# usb2serial.net
KiCad netlist of a schematic drawn in EAGLE
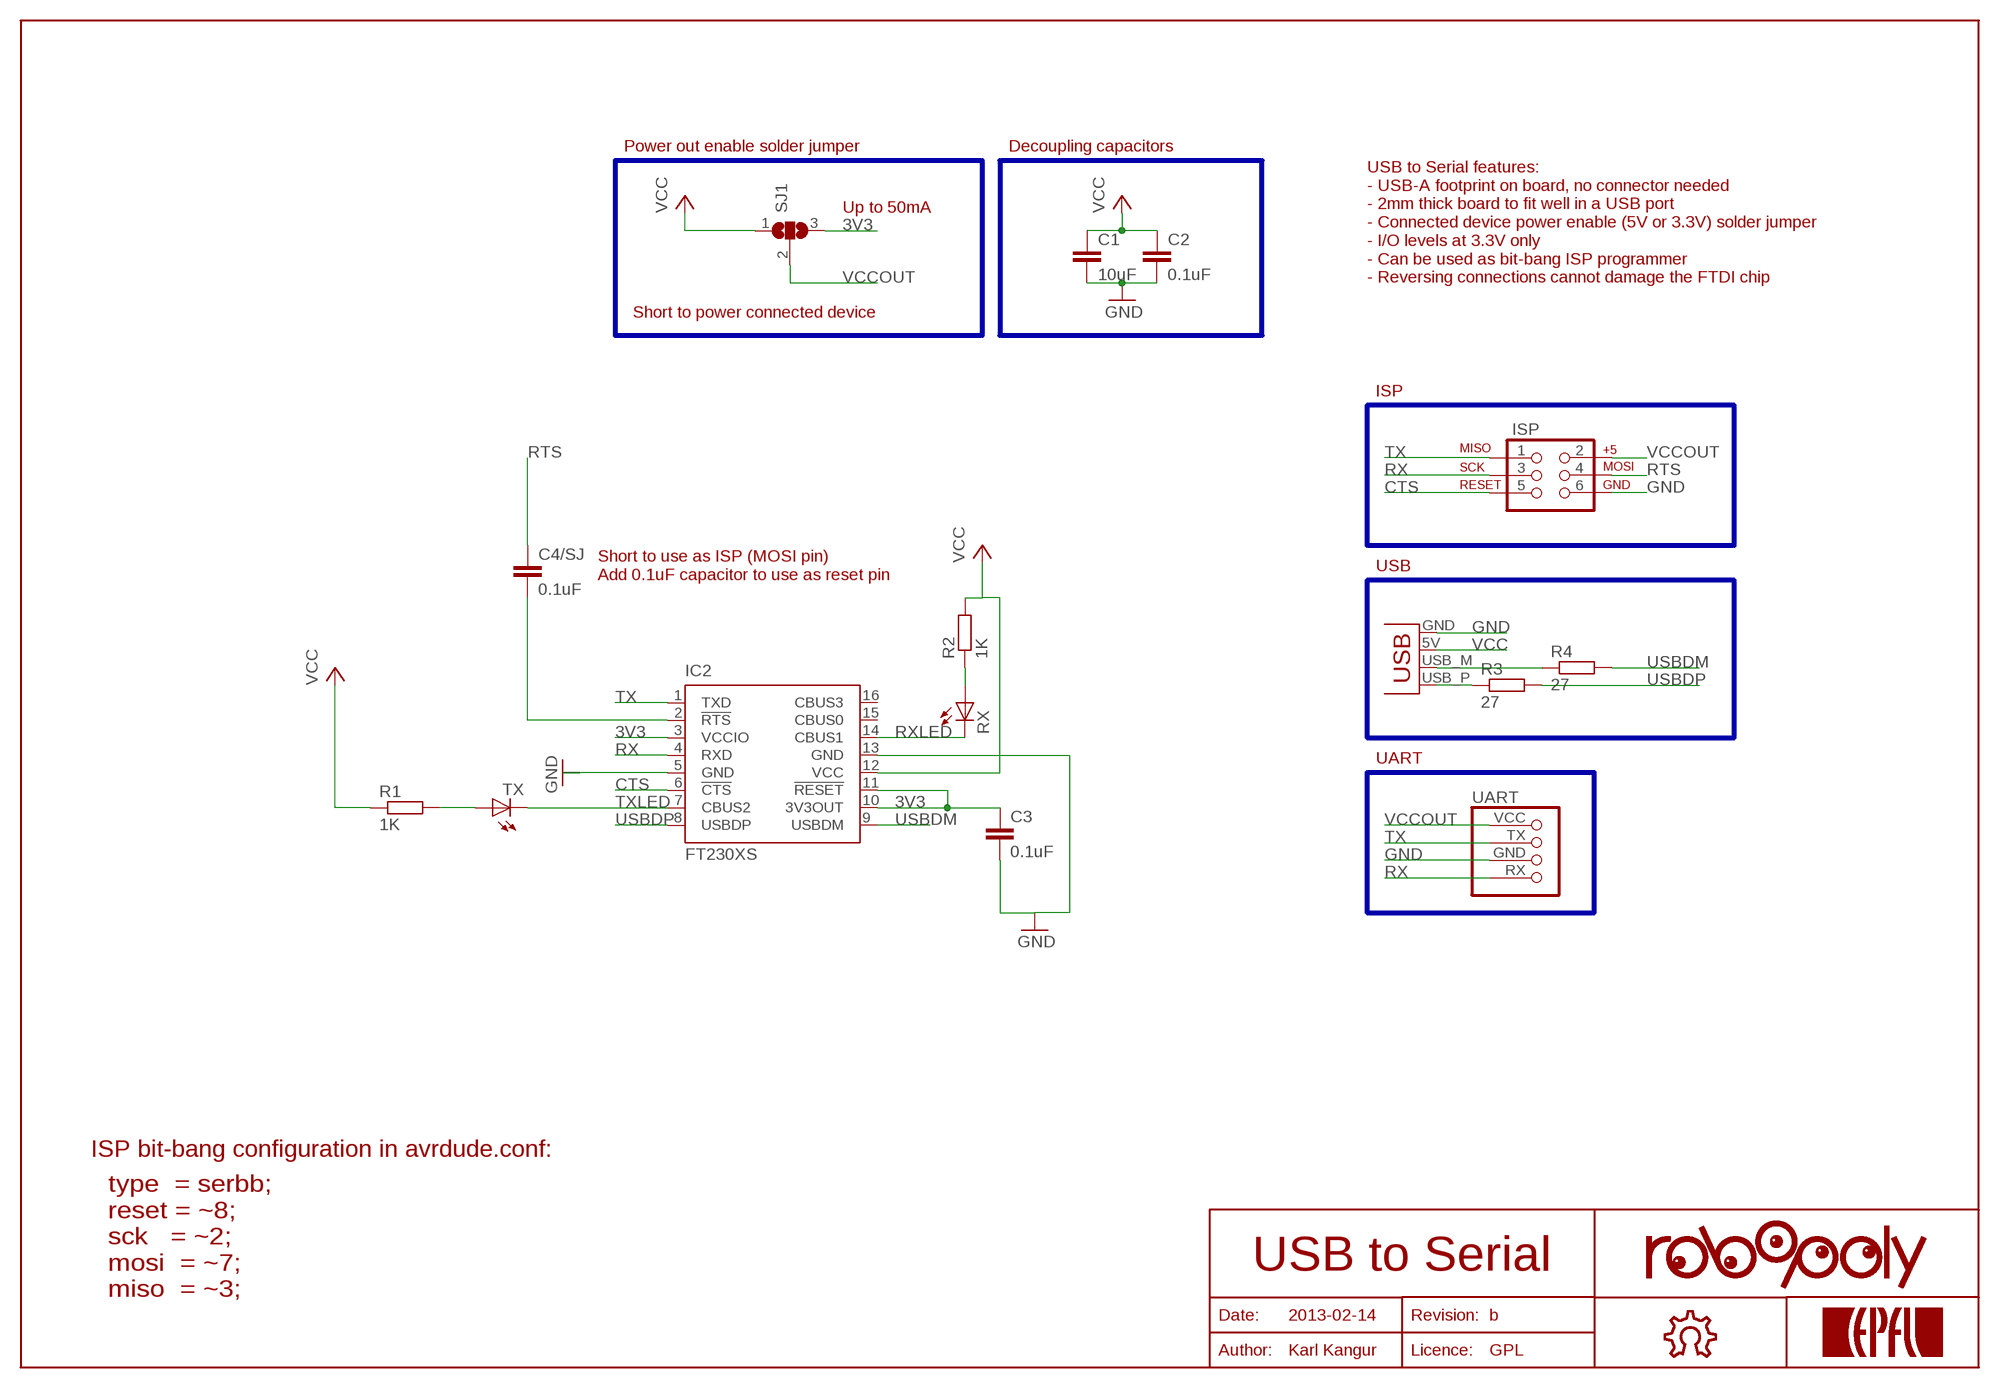
[diagram p0: schematic, sheet 1]

(export (version "E")
  (design (tool "Eeschema 10.0.6"))
  (components
    (comp (ref "C1")
      (value "10uF")
      (footprint "eagle-import:C0805")
      (libsource (lib "eagle-import") (part "C-EUC0805"))
    )
    (comp (ref "C2")
      (value "0.1uF")
      (footprint "eagle-import:C0805")
      (libsource (lib "eagle-import") (part "C-EUC0805"))
    )
    (comp (ref "C3")
      (value "0.1uF")
      (footprint "eagle-import:C0805")
      (libsource (lib "eagle-import") (part "C-EUC0805"))
    )
    (comp (ref "C4/SJ")
      (value "0.1uF")
      (footprint "eagle-import:C0805")
      (libsource (lib "eagle-import") (part "C-EUC0805"))
    )
    (comp (ref "IC2")
      (value "FT230XS")
      (footprint "eagle-import:SSOP16")
      (libsource (lib "eagle-import") (part "FT230XS"))
    )
    (comp (ref "ISP")
      (value "ISP-6PIN")
      (footprint "eagle-import:2X3")
      (libsource (lib "eagle-import") (part "ISP-6PIN"))
    )
    (comp (ref "JP1")
      (value "USBPCB")
      (footprint "eagle-import:USB-A-PCB")
      (libsource (lib "eagle-import") (part "USBPCB"))
    )
    (comp (ref "R1")
      (value "1K")
      (footprint "eagle-import:R0805")
      (libsource (lib "eagle-import") (part "R-EU_R0805"))
    )
    (comp (ref "R2")
      (value "1K")
      (footprint "eagle-import:R0805")
      (libsource (lib "eagle-import") (part "R-EU_R0805"))
    )
    (comp (ref "R3")
      (value "27")
      (footprint "eagle-import:R0805")
      (libsource (lib "eagle-import") (part "R-EU_R0805"))
    )
    (comp (ref "R4")
      (value "27")
      (footprint "eagle-import:R0805")
      (libsource (lib "eagle-import") (part "R-EU_R0805"))
    )
    (comp (ref "RX")
      (value "LEDCHIPLED_0805")
      (footprint "eagle-import:CHIPLED_0805")
      (libsource (lib "eagle-import") (part "LEDCHIPLED_0805"))
    )
    (comp (ref "SJ1")
      (value "SJ2W")
      (footprint "eagle-import:SJ_2")
      (libsource (lib "eagle-import") (part "SJ2W"))
    )
    (comp (ref "TX")
      (value "LEDCHIPLED_0805")
      (footprint "eagle-import:CHIPLED_0805")
      (libsource (lib "eagle-import") (part "LEDCHIPLED_0805"))
    )
    (comp (ref "U$1")
      (value "UART-ROBOPOLY90")
      (footprint "eagle-import:929835-01-04-RK")
      (libsource (lib "eagle-import") (part "UART-ROBOPOLY90"))
    )
    (comp (ref "U$2")
      (value "ROBOPOLY-LOGOBOTTOM")
      (footprint "eagle-import:ROBOPOLY-LOGO-BOTTOM")
      (libsource (lib "eagle-import") (part "ROBOPOLY-LOGOBOTTOM"))
    )
    (comp (ref "U$3")
      (value "OPEN-HARDWARE-LOGOBOTTOM-SMALL")
      (footprint "eagle-import:OPEN-HARDWARE-BOTTOM-SMALL")
      (libsource (lib "eagle-import") (part "OPEN-HARDWARE-LOGOBOTTOM-SMALL"))
    )
  )
  (nets
    (net (code "1") (name "/3V3") (class "Default")
      (node (ref "C3") (pin "1") (pinfunction "1_1") (pintype "passive"))
      (node (ref "IC2") (pin "10") (pinfunction "3V3OUT_10") (pintype "output"))
      (node (ref "IC2") (pin "11") (pinfunction "~{RESET}_11") (pintype "input"))
      (node (ref "IC2") (pin "3") (pinfunction "VCCIO_3") (pintype "power_in"))
      (node (ref "SJ1") (pin "3") (pinfunction "3_3") (pintype "passive"))
    )
    (net (code "2") (name "/CTS") (class "Default")
      (node (ref "IC2") (pin "6") (pinfunction "~{CTS}_6") (pintype "input"))
      (node (ref "ISP") (pin "5") (pinfunction "5_5") (pintype "passive"))
    )
    (net (code "3") (name "/RTS") (class "Default")
      (node (ref "C4/SJ") (pin "1") (pinfunction "1_1") (pintype "passive"))
      (node (ref "ISP") (pin "4") (pinfunction "4_4") (pintype "passive"))
    )
    (net (code "4") (name "/RX") (class "Default")
      (node (ref "IC2") (pin "4") (pinfunction "RXD_4") (pintype "input"))
      (node (ref "ISP") (pin "3") (pinfunction "3_3") (pintype "passive"))
      (node (ref "U$1") (pin "RX") (pinfunction "4_RX") (pintype "passive"))
    )
    (net (code "5") (name "/RXLED") (class "Default")
      (node (ref "IC2") (pin "14") (pinfunction "CBUS1_14") (pintype "bidirectional"))
      (node (ref "RX") (pin "C") (pinfunction "C_C") (pintype "passive"))
    )
    (net (code "6") (name "/TX") (class "Default")
      (node (ref "IC2") (pin "1") (pinfunction "TXD_1") (pintype "output"))
      (node (ref "ISP") (pin "1") (pinfunction "1_1") (pintype "passive"))
      (node (ref "U$1") (pin "TX") (pinfunction "2_TX") (pintype "passive"))
    )
    (net (code "7") (name "/TXLED") (class "Default")
      (node (ref "IC2") (pin "7") (pinfunction "CBUS2_7") (pintype "bidirectional"))
      (node (ref "TX") (pin "C") (pinfunction "C_C") (pintype "passive"))
    )
    (net (code "8") (name "/USBDM") (class "Default")
      (node (ref "IC2") (pin "9") (pinfunction "USBDM_9") (pintype "input"))
      (node (ref "R4") (pin "2") (pinfunction "2_2") (pintype "passive"))
    )
    (net (code "9") (name "/USBDP") (class "Default")
      (node (ref "IC2") (pin "8") (pinfunction "USBDP_8") (pintype "input"))
      (node (ref "R3") (pin "2") (pinfunction "2_2") (pintype "passive"))
    )
    (net (code "10") (name "/VCCOUT") (class "Default")
      (node (ref "ISP") (pin "2") (pinfunction "2_2") (pintype "passive"))
      (node (ref "SJ1") (pin "2") (pinfunction "2_2") (pintype "passive"))
      (node (ref "U$1") (pin "VCC") (pinfunction "1_VCC") (pintype "passive"))
    )
    (net (code "11") (name "GND") (class "Default")
      (node (ref "C1") (pin "2") (pinfunction "2_2") (pintype "passive"))
      (node (ref "C2") (pin "2") (pinfunction "2_2") (pintype "passive"))
      (node (ref "C3") (pin "2") (pinfunction "2_2") (pintype "passive"))
      (node (ref "IC2") (pin "13") (pinfunction "GND_13") (pintype "power_in"))
      (node (ref "IC2") (pin "5") (pinfunction "GND_5") (pintype "power_in"))
      (node (ref "ISP") (pin "6") (pinfunction "6_6") (pintype "passive"))
      (node (ref "JP1") (pin "GND") (pinfunction "GND_GND") (pintype "bidirectional"))
      (node (ref "U$1") (pin "GND") (pinfunction "3_GND") (pintype "passive"))
    )
    (net (code "12") (name "Net-(IC2-~{RTS})") (class "Default")
      (node (ref "C4/SJ") (pin "2") (pinfunction "2_2") (pintype "passive"))
      (node (ref "IC2") (pin "2") (pinfunction "~{RTS}_2") (pintype "output"))
    )
    (net (code "13") (name "Net-(JP1-D+)") (class "Default")
      (node (ref "JP1") (pin "USB_P") (pinfunction "D+_USB_P") (pintype "bidirectional"))
      (node (ref "R3") (pin "1") (pinfunction "1_1") (pintype "passive"))
    )
    (net (code "14") (name "Net-(JP1-D-)") (class "Default")
      (node (ref "JP1") (pin "USB_M") (pinfunction "D-_USB_M") (pintype "bidirectional"))
      (node (ref "R4") (pin "1") (pinfunction "1_1") (pintype "passive"))
    )
    (net (code "15") (name "Net-(R1-Pad2)") (class "Default")
      (node (ref "R1") (pin "2") (pinfunction "2_2") (pintype "passive"))
      (node (ref "TX") (pin "A") (pinfunction "A_A") (pintype "passive"))
    )
    (net (code "16") (name "Net-(R2-Pad1)") (class "Default")
      (node (ref "R2") (pin "1") (pinfunction "1_1") (pintype "passive"))
      (node (ref "RX") (pin "A") (pinfunction "A_A") (pintype "passive"))
    )
    (net (code "17") (name "VCC") (class "Default")
      (node (ref "C1") (pin "1") (pinfunction "1_1") (pintype "passive"))
      (node (ref "C2") (pin "1") (pinfunction "1_1") (pintype "passive"))
      (node (ref "IC2") (pin "12") (pinfunction "VCC_12") (pintype "power_in"))
      (node (ref "JP1") (pin "5V") (pinfunction "VBUS_5V") (pintype "bidirectional"))
      (node (ref "R1") (pin "1") (pinfunction "1_1") (pintype "passive"))
      (node (ref "R2") (pin "2") (pinfunction "2_2") (pintype "passive"))
      (node (ref "SJ1") (pin "1") (pinfunction "1_1") (pintype "passive"))
    )
    (net (code "18") (name "unconnected-(IC2-CBUS0-Pad15)") (class "Default")
      (node (ref "IC2") (pin "15") (pinfunction "CBUS0_15") (pintype "bidirectional"))
    )
    (net (code "19") (name "unconnected-(IC2-CBUS3-Pad16)") (class "Default")
      (node (ref "IC2") (pin "16") (pinfunction "CBUS3_16") (pintype "bidirectional"))
    )
  )
)
